# PoE_Si3404.net
KiCad netlist of a schematic drawn in Altium Designer
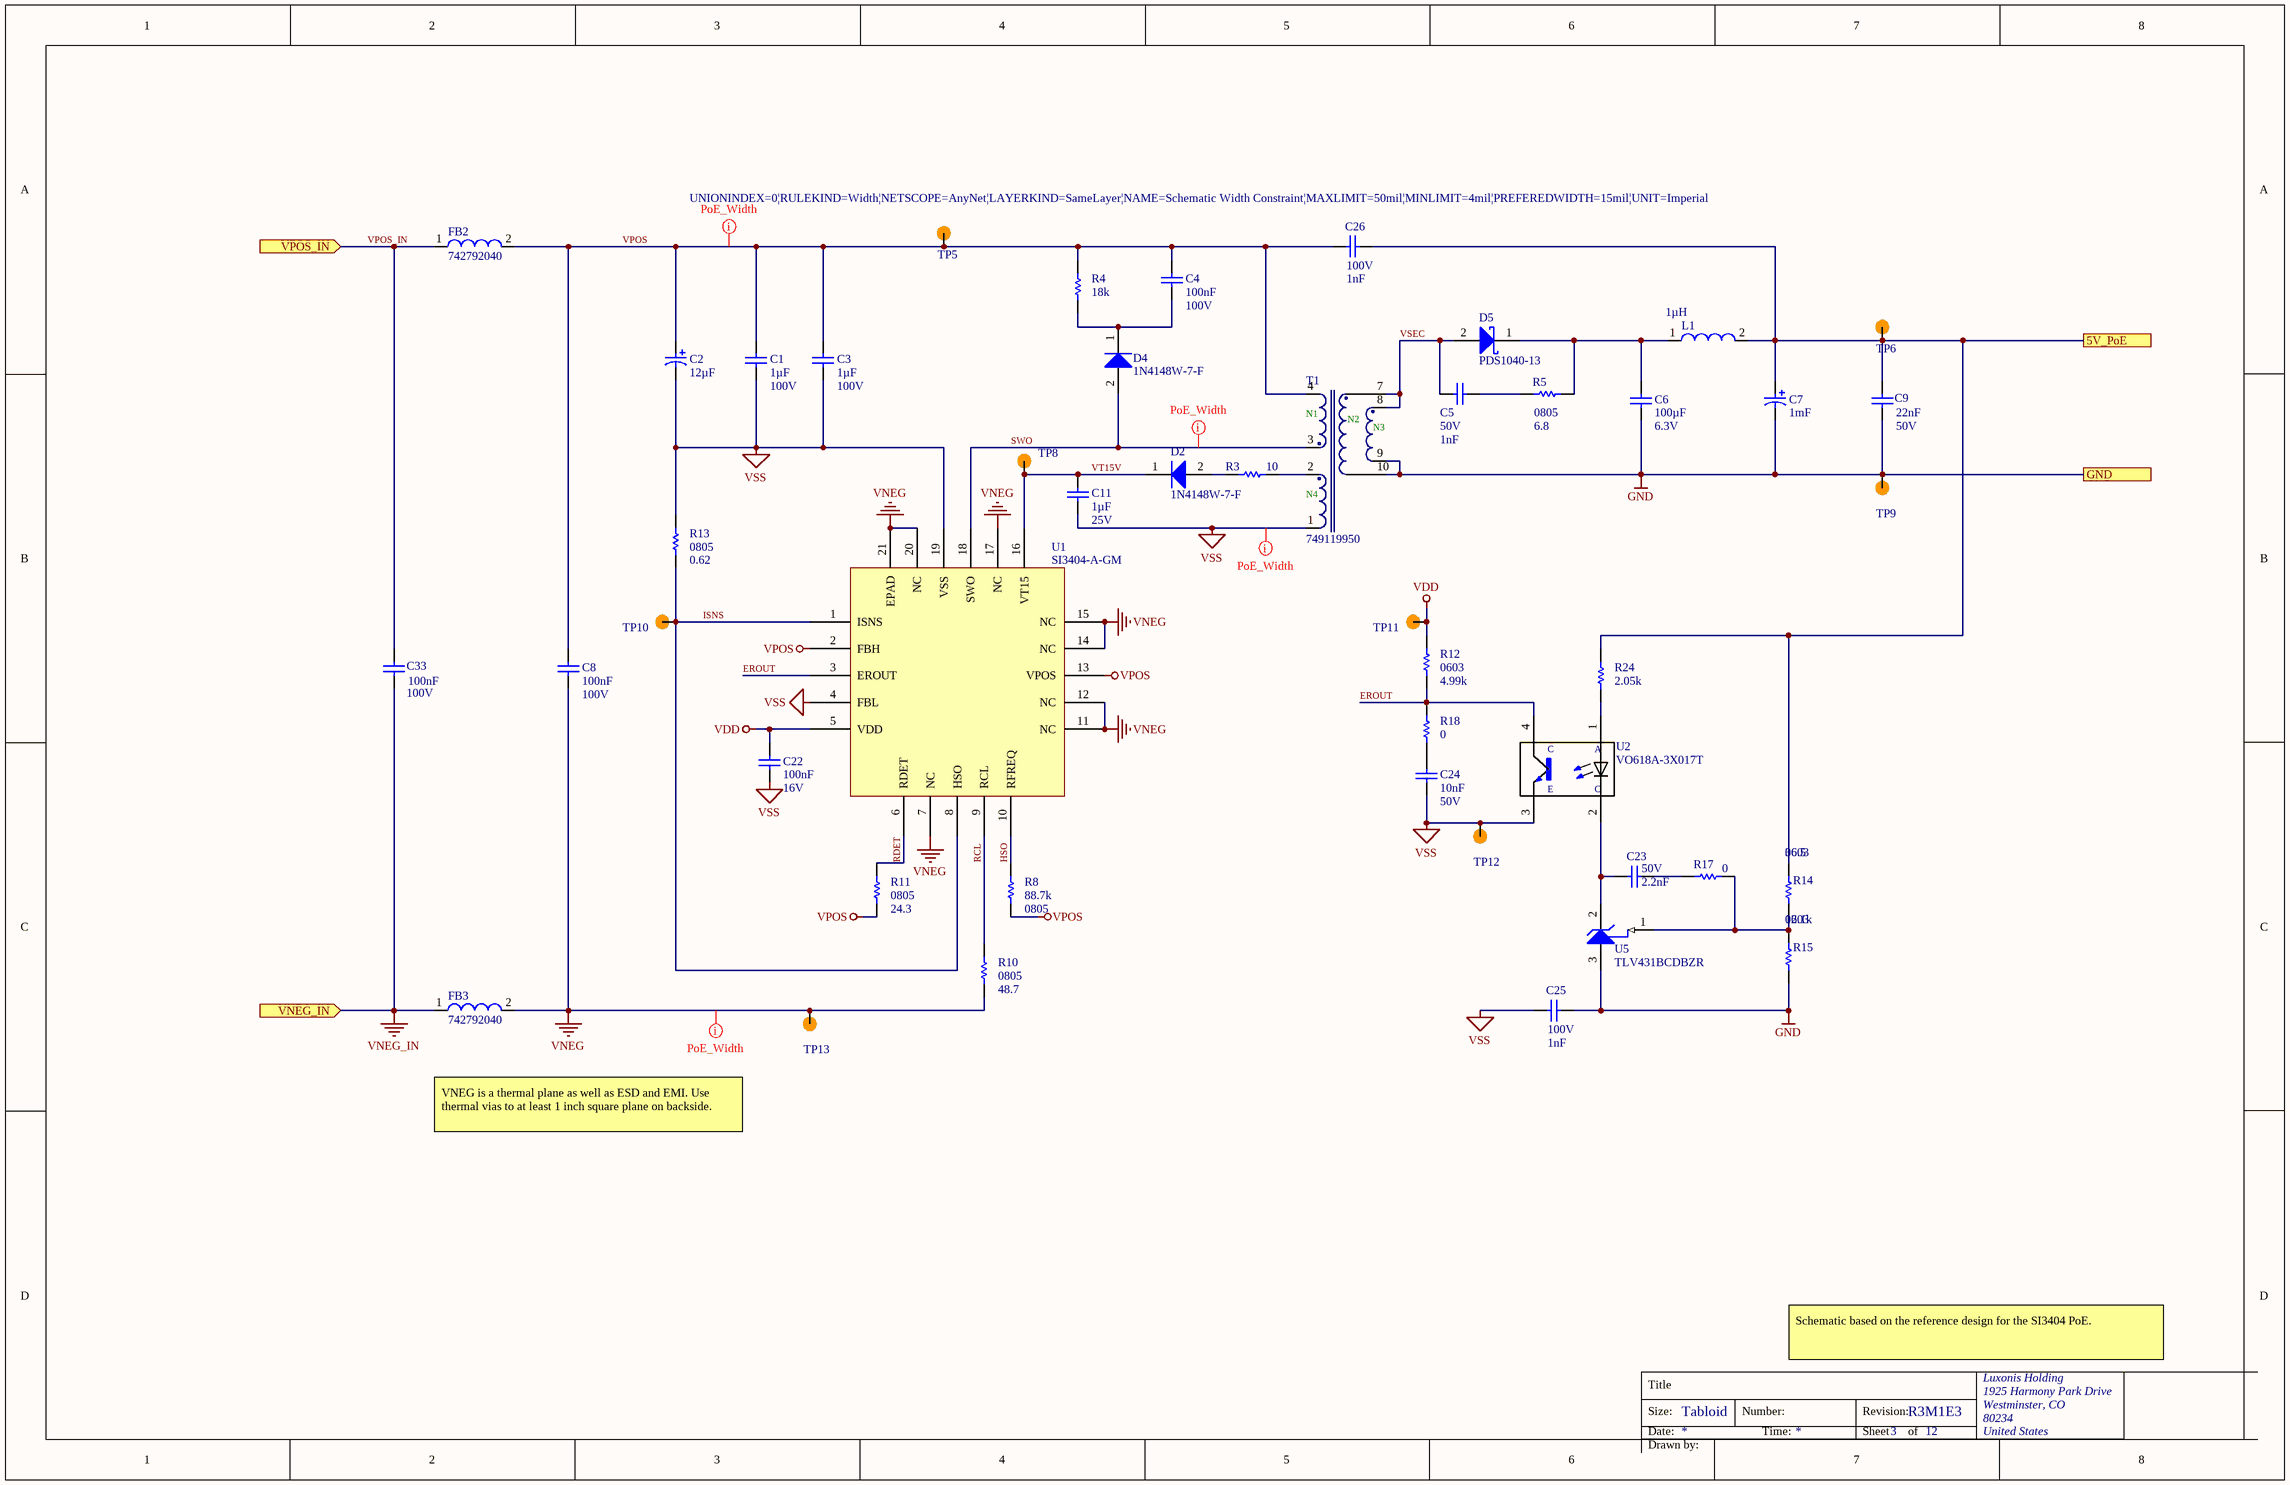
[diagram p0: PoE_Si3404.SchDoc]

(export (version "E")
  (design (tool "Eeschema 10.0.6"))
  (components
    (comp (ref "C1")
      (value "1µF")
      (footprint "CAPC1210(3225)280_N")
      (description "CAP CER 1UF 100V X7R 1210 10%")
      (fields
        (field (name "TOLERANCE") "10%")
        (field (name "VOLTAGE RATING") "100V")
        (field (name "Comment") "CL32B105KCJNNNE")
      )
      (libsource (lib "Luxonis LLC") (part "GRM188R61C475KAAJD"))
    )
    (comp (ref "C2")
      (value "12µF")
      (footprint "EEU-FC2A120")
      (description "CAP ALUM 12UF 100V RADIAL 20%")
      (fields (field (name "TOLERANCE") "20%") (field (name "Comment") "EEU-FC2A120"))
      (libsource (lib "Luxonis LLC") (part "EEU-FC2A120"))
    )
    (comp (ref "C3")
      (value "1µF")
      (footprint "CAPC1210(3225)280_N")
      (description "CAP CER 1UF 100V X7R 1210 10%")
      (fields
        (field (name "TOLERANCE") "10%")
        (field (name "VOLTAGE RATING") "100V")
        (field (name "Comment") "CL32B105KCJNNNE")
      )
      (libsource (lib "Luxonis LLC") (part "GRM188R61C475KAAJD"))
    )
    (comp (ref "C4")
      (value "100nF")
      (footprint "CAPC0805(2012)145_N")
      (description "CAP CER 0.1UF 100V X7R 0805 10%")
      (fields
        (field (name "TOLERANCE") "10%")
        (field (name "VOLTAGE RATING") "100V")
        (field (name "Comment") "CL21B104KCFNNNE")
      )
      (libsource (lib "Luxonis LLC") (part "GRM188R61C475KAAJD"))
    )
    (comp (ref "C5")
      (value "1nF")
      (footprint "CAPC0603(1608)100_N")
      (description "CAP CER 1000PF 50V C0G 0603 1%")
      (fields
        (field (name "TOLERANCE") "1%")
        (field (name "VOLTAGE RATING") "50V")
        (field (name "Comment") "GRM1885C1H102FA01D")
      )
      (libsource (lib "Luxonis LLC") (part "LLL153C70G474ME17E"))
    )
    (comp (ref "C6")
      (value "100µF")
      (footprint "CAPC1206(3216)190_N")
      (description "CAP CER 100UF 6.3V X5R 1206 20%")
      (fields
        (field (name "TOLERANCE") "20%")
        (field (name "VOLTAGE RATING") "6.3V")
        (field (name "Comment") "CL31A107MQHNNNE")
      )
      (libsource (lib "Luxonis LLC") (part "GRM188R61C475KAAJD"))
    )
    (comp (ref "C7")
      (value "1mF")
      (footprint "ECA-0JM102")
      (description "CAP ALUM 1000UF 6.3V RADIAL 20%")
      (fields (field (name "TOLERANCE") "20%") (field (name "Comment") "ECA-0JM102"))
      (libsource (lib "Luxonis LLC") (part "EEU-FC2A120"))
    )
    (comp (ref "C8")
      (value "100nF")
      (footprint "CAPC0805(2012)145_N")
      (description "CAP CER 0.1UF 100V X7R 0805 10%")
      (fields
        (field (name "TOLERANCE") "10%")
        (field (name "VOLTAGE RATING") "100V")
        (field (name "Comment") "CL21B104KCFNNNE")
      )
      (libsource (lib "Luxonis LLC") (part "GRM188R61C475KAAJD"))
    )
    (comp (ref "C9")
      (value "22nF")
      (footprint "CAPC0603(1608)100_N")
      (description "CAP CER 0.022UF 50V X7R 0603 10%")
      (fields
        (field (name "TOLERANCE") "10%")
        (field (name "VOLTAGE RATING") "50V")
        (field (name "Comment") "C0603C223K5RACTU")
      )
      (libsource (lib "Luxonis LLC") (part "LLL153C70G474ME17E"))
    )
    (comp (ref "C11")
      (value "1µF")
      (footprint "CAPC0402(1005)70_N")
      (description "CAP CER 1UF 25V X5R 0402 10%")
      (fields
        (field (name "TOLERANCE") "10%")
        (field (name "VOLTAGE RATING") "25V")
        (field (name "Comment") "GRM155R61E105KA12D")
      )
      (libsource (lib "Luxonis LLC") (part "GRM188R61C475KAAJD"))
    )
    (comp (ref "C22")
      (value "100nF")
      (footprint "CAPC0402(1005)60_N")
      (description "CAP CER 0.1UF 16V X7R 0402 10%")
      (fields
        (field (name "TOLERANCE") "10%")
        (field (name "VOLTAGE RATING") "16V")
        (field (name "Comment") "CL05B104KO5NFNC")
      )
      (libsource (lib "Luxonis LLC") (part "GRM188R61C475KAAJD"))
    )
    (comp (ref "C23")
      (value "2.2nF")
      (footprint "CAPC0603(1608)100_N")
      (description "CAP CER 2200PF 50V C0G 0603 5%")
      (fields
        (field (name "TOLERANCE") "5%")
        (field (name "VOLTAGE RATING") "50V")
        (field (name "Comment") "GRM1885C1H222JA01D")
      )
      (libsource (lib "Luxonis LLC") (part "GRM188R61C475KAAJD"))
    )
    (comp (ref "C24")
      (value "10nF")
      (footprint "CAPC0402(1005)60_N")
      (description "CAP CER 10000PF 50V X7R 0402 10%")
      (fields
        (field (name "TOLERANCE") "10%")
        (field (name "VOLTAGE RATING") "50V")
        (field (name "Comment") "GRM155R71H103KA88D")
      )
      (libsource (lib "Luxonis LLC") (part "GRM188R61C475KAAJD"))
    )
    (comp (ref "C25")
      (value "1nF")
      (footprint "CAPC1206(3216)130_L")
      (description "CAP CER 1nF 2000V X7R 1206 10%")
      (fields
        (field (name "TOLERANCE") "10%")
        (field (name "VOLTAGE RATING") "100V")
        (field (name "Comment") "C1206C102KGRACTU")
      )
      (libsource (lib "Luxonis LLC") (part "LLL153C70G474ME17E"))
    )
    (comp (ref "C26")
      (value "1nF")
      (footprint "CAPC1206(3216)130_L")
      (description "CAP CER 1nF 2000V X7R 1206 10%")
      (fields
        (field (name "TOLERANCE") "10%")
        (field (name "VOLTAGE RATING") "100V")
        (field (name "Comment") "C1206C102KGRACTU")
      )
      (libsource (lib "Luxonis LLC") (part "LLL153C70G474ME17E"))
    )
    (comp (ref "C33")
      (value "100nF")
      (footprint "CAPC0805(2012)145_N")
      (description "CAP CER 0.1UF 100V X7R 0805 10%")
      (fields
        (field (name "TOLERANCE") "10%")
        (field (name "VOLTAGE RATING") "100V")
        (field (name "Comment") "CL21B104KCFNNNE")
      )
      (libsource (lib "Luxonis LLC") (part "GRM188R61C475KAAJD"))
    )
    (comp (ref "D2")
      (value "1N4148W-7-F")
      (footprint "1N4148W-7-F")
      (description "DIODE GEN PURP 100V 300MA SOD123")
      (libsource (lib "Luxonis LLC") (part "1N4148W-7-F"))
    )
    (comp (ref "D4")
      (value "1N4148W-7-F")
      (footprint "RS1B")
      (description "DIODE GEN PURP 100V 1A SMA")
      (libsource (lib "Luxonis LLC") (part "1N4148W-7-F"))
    )
    (comp (ref "D5")
      (value "PDS1040-13")
      (footprint "PDS1040-13")
      (description "DIODE SCHOTTKY 40V 10A POWERDI5")
      (libsource (lib "Luxonis LLC") (part "PDS1040-13"))
    )
    (comp (ref "FB2")
      (value "742792040")
      (footprint "742792040")
      (description "FERRITE BEAD 600 OHM 0805 1LN")
      (fields (field (name "TOLERANCE") "25%"))
      (libsource (lib "Luxonis LLC") (part "742792040"))
    )
    (comp (ref "FB3")
      (value "742792040")
      (footprint "742792040")
      (description "FERRITE BEAD 600 OHM 0805 1LN")
      (fields (field (name "TOLERANCE") "25%"))
      (libsource (lib "Luxonis LLC") (part "742792040"))
    )
    (comp (ref "L1")
      (value "1µH")
      (footprint "DO1608C-102MLx")
      (description "IND POWER WIREWOUND 1uH 20% 100KHz FERRITE 2.7A")
      (fields (field (name "TOLERANCE") "20%") (field (name "Comment") "DO1608C-102ML"))
      (libsource (lib "Luxonis LLC") (part "DFE252012P-1R0M=P2"))
    )
    (comp (ref "R3")
      (value "10")
      (footprint "RESC0603(1608)_N")
      (description "RES SMD 10 OHM 1% 1/10W 0603")
      (fields (field (name "TOLERANCE") "1%") (field (name "Comment") "CRCW060310R0FKEA"))
      (libsource (lib "Luxonis LLC") (part "RC0402FR-0722RL_1"))
    )
    (comp (ref "R4")
      (value "18k")
      (footprint "RESC0603(1608)_N")
      (description "RES SMD 18K OHM 5% 1/10W 0603")
      (fields (field (name "TOLERANCE") "5%") (field (name "Comment") "RC0603JR-0718KL"))
      (libsource (lib "Luxonis LLC") (part "RC0402FR-0722RL_1"))
    )
    (comp (ref "R5")
      (value "6.8")
      (footprint "RESC0805(2012)_N")
      (description "RES SMD 6.8 OHM 1% 1/8W 0805")
      (fields
        (field (name "CASE/PACKAGE") "0805")
        (field (name "TOLERANCE") "1%")
        (field (name "Comment") "RC0805FR-076R8L")
      )
      (libsource (lib "Luxonis LLC") (part "Default resistor symbol"))
    )
    (comp (ref "R8")
      (value "88.7k")
      (footprint "RESC0805(2012)_N")
      (description "RES SMD 88.7K OHM 1% 1/8W 0805")
      (fields
        (field (name "CASE/PACKAGE") "0805")
        (field (name "TOLERANCE") "1%")
        (field (name "Comment") "CRCW080588K7FKEA")
      )
      (libsource (lib "Luxonis LLC") (part "Default resistor symbol"))
    )
    (comp (ref "R10")
      (value "48.7")
      (footprint "RESC0805(2012)_N")
      (description "RES SMD 48.7 OHM 1% 1/8W 0805")
      (fields
        (field (name "CASE/PACKAGE") "0805")
        (field (name "TOLERANCE") "1%")
        (field (name "Comment") "RC0805FR-0748R7L")
      )
      (libsource (lib "Luxonis LLC") (part "Default resistor symbol"))
    )
    (comp (ref "R11")
      (value "24.3")
      (footprint "RESC0805(2012)_N")
      (description "RES SMD 24.3K OHM 1% 1/8W 0805")
      (fields
        (field (name "CASE/PACKAGE") "0805")
        (field (name "TOLERANCE") "1%")
        (field (name "Comment") "CRCW080524K3FKEA")
      )
      (libsource (lib "Luxonis LLC") (part "Default resistor symbol"))
    )
    (comp (ref "R12")
      (value "4.99k")
      (footprint "RESC0603(1608)_N")
      (description "RES SMD 4.99K OHM 1% 1/10W 0603")
      (fields
        (field (name "CASE/PACKAGE") "0603")
        (field (name "TOLERANCE") "1%")
        (field (name "Comment") "RC0603FR-074K99L")
      )
      (libsource (lib "Luxonis LLC") (part "Default resistor symbol"))
    )
    (comp (ref "R13")
      (value "0.62")
      (footprint "RESC0805(2012)_N")
      (description "RES SMD 620 MOHM 1% 1/8W 0805")
      (fields
        (field (name "CASE/PACKAGE") "0805")
        (field (name "TOLERANCE") "1%")
        (field (name "Comment") "RL0805FR-070R62L")
      )
      (libsource (lib "Luxonis LLC") (part "Default resistor symbol"))
    )
    (comp (ref "R14")
      (value "36.5")
      (footprint "RESC0603(1608)_N")
      (description "RES SMD 36.5K OHM 1% 1/10W 0603")
      (fields
        (field (name "CASE/PACKAGE") "0603")
        (field (name "TOLERANCE") "1%")
        (field (name "Comment") "RC0603FR-0736K5L")
      )
      (libsource (lib "Luxonis LLC") (part "Default resistor symbol"))
    )
    (comp (ref "R15")
      (value "12.1k")
      (footprint "RESC0603(1608)_N")
      (description "RES SMD 12.1K OHM 1% 1/10W 0603")
      (fields
        (field (name "CASE/PACKAGE") "0603")
        (field (name "TOLERANCE") "1%")
        (field (name "Comment") "RC0603FR-0712K1L")
      )
      (libsource (lib "Luxonis LLC") (part "Default resistor symbol"))
    )
    (comp (ref "R17")
      (value "0")
      (footprint "RESC0603(1608)_N")
      (description "RES SMD 0 OHM 5% 1/10W 0603")
      (fields (field (name "TOLERANCE") "5%") (field (name "Comment") "CRCW06030000Z0EA"))
      (libsource (lib "Luxonis LLC") (part "RC0402FR-0722RL_1"))
    )
    (comp (ref "R18")
      (value "0")
      (footprint "RESC0603(1608)_N")
      (description "RES SMD 0 OHM 5% 1/10W 0603")
      (fields (field (name "TOLERANCE") "5%") (field (name "Comment") "CRCW06030000Z0EA"))
      (libsource (lib "Luxonis LLC") (part "RC0402FR-0722RL_1"))
    )
    (comp (ref "R24")
      (value "2.05k")
      (footprint "RESC0603(1608)_N")
      (description "RES SMD 2.05K OHM 1% 1/10W 0603")
      (fields (field (name "TOLERANCE") "1%") (field (name "Comment") "RC0603FR-072K05L"))
      (libsource (lib "Luxonis LLC") (part "RC0402FR-0722RL_1"))
    )
    (comp (ref "T1")
      (value "749119950")
      (footprint "749119950")
      (description "TRANS FLYBACK POE 127UH SMD")
      (libsource (lib "Luxonis LLC") (part "749119950"))
    )
    (comp (ref "TP5")
      (value "TEST_POINT")
      (footprint "TP100_200_NS")
      (libsource (lib "Luxonis LLC") (part "TEST_POINT"))
    )
    (comp (ref "TP6")
      (value "TEST_POINT")
      (footprint "TP100_200_NS")
      (libsource (lib "Luxonis LLC") (part "TEST_POINT"))
    )
    (comp (ref "TP8")
      (value "TEST_POINT")
      (footprint "TP100_200_NS")
      (libsource (lib "Luxonis LLC") (part "TEST_POINT"))
    )
    (comp (ref "TP9")
      (value "TEST_POINT")
      (footprint "TP100_200_NS")
      (libsource (lib "Luxonis LLC") (part "TEST_POINT"))
    )
    (comp (ref "TP10")
      (value "TEST_POINT")
      (footprint "TP100_200_NS")
      (libsource (lib "Luxonis LLC") (part "TEST_POINT"))
    )
    (comp (ref "TP11")
      (value "TEST_POINT")
      (footprint "TP100_200_NS")
      (libsource (lib "Luxonis LLC") (part "TEST_POINT"))
    )
    (comp (ref "TP12")
      (value "TEST_POINT")
      (footprint "TP100_200_NS")
      (libsource (lib "Luxonis LLC") (part "TEST_POINT"))
    )
    (comp (ref "TP13")
      (value "TEST_POINT")
      (footprint "TP100_200_NS")
      (libsource (lib "Luxonis LLC") (part "TEST_POINT"))
    )
    (comp (ref "U1")
      (value "SI3404-A-GM")
      (footprint "Si3404-A-GM")
      (description "IC POE CNTRL 1 CHANNEL 20QFN")
      (libsource (lib "Luxonis LLC") (part "SI3404-A-GM"))
    )
    (comp (ref "U2")
      (value "VO618A-3X017T")
      (footprint "VO618A-3X017T")
      (description "OPTOISOLATOR 5.3KV TRANS 4-SMD")
      (libsource (lib "Luxonis LLC") (part "VO618A-3X017T"))
    )
    (comp (ref "U5")
      (value "TLV431BCDBZR")
      (footprint "TLV431BCDBZR")
      (description "IC VREF SHUNT ADJ SOT23-3")
      (libsource (lib "Luxonis LLC") (part "TLV431BCDBZR"))
    )
  )
  (nets
    (net (code "1") (name "/5V_PoE") (class "Default")
      (node (ref "C26") (pin "2") (pinfunction "2_2") (pintype "passive"))
      (node (ref "C7") (pin "1") (pinfunction "1_1") (pintype "passive"))
      (node (ref "C9") (pin "2") (pinfunction "2_2") (pintype "passive"))
      (node (ref "L1") (pin "2") (pinfunction "2_2") (pintype "passive"))
      (node (ref "R14") (pin "2") (pinfunction "2_2") (pintype "passive"))
      (node (ref "R24") (pin "2") (pinfunction "2_2") (pintype "passive"))
      (node (ref "TP6") (pin "1") (pintype "passive"))
    )
    (net (code "2") (name "/EROUT") (class "Default")
      (node (ref "R12") (pin "1") (pinfunction "1_1") (pintype "passive"))
      (node (ref "R18") (pin "2") (pinfunction "2_2") (pintype "passive"))
      (node (ref "U1") (pin "3") (pinfunction "EROUT_3") (pintype "passive"))
      (node (ref "U2") (pin "4") (pinfunction "CO_4") (pintype "passive"))
    )
    (net (code "3") (name "/HSO") (class "Default")
      (node (ref "R8") (pin "2") (pinfunction "2_2") (pintype "passive"))
      (node (ref "U1") (pin "10") (pinfunction "RFREQ_10") (pintype "passive"))
    )
    (net (code "4") (name "/ISNS") (class "Default")
      (node (ref "R13") (pin "1") (pinfunction "1_1") (pintype "passive"))
      (node (ref "TP10") (pin "1") (pintype "passive"))
      (node (ref "U1") (pin "1") (pinfunction "ISNS_1") (pintype "passive"))
      (node (ref "U1") (pin "8") (pinfunction "HSO_8") (pintype "passive"))
    )
    (net (code "5") (name "/RCL") (class "Default")
      (node (ref "R10") (pin "2") (pinfunction "2_2") (pintype "passive"))
      (node (ref "U1") (pin "9") (pinfunction "RCL_9") (pintype "passive"))
    )
    (net (code "6") (name "/RDET") (class "Default")
      (node (ref "R11") (pin "2") (pinfunction "2_2") (pintype "passive"))
      (node (ref "U1") (pin "6") (pinfunction "RDET_6") (pintype "passive"))
    )
    (net (code "7") (name "/SWO") (class "Default")
      (node (ref "D4") (pin "2") (pinfunction "A_2") (pintype "passive"))
      (node (ref "T1") (pin "3") (pinfunction "3_3") (pintype "passive"))
      (node (ref "U1") (pin "18") (pinfunction "SWO_18") (pintype "passive"))
    )
    (net (code "8") (name "/VPOS_IN") (class "Default")
      (node (ref "C33") (pin "2") (pinfunction "2_2") (pintype "passive"))
      (node (ref "FB2") (pin "1") (pinfunction "1_1") (pintype "passive"))
    )
    (net (code "9") (name "/VSEC") (class "Default")
      (node (ref "C5") (pin "2") (pinfunction "2_2") (pintype "passive"))
      (node (ref "D5") (pin "2") (pinfunction "A_2") (pintype "passive"))
      (node (ref "T1") (pin "7") (pinfunction "7_7") (pintype "passive"))
      (node (ref "T1") (pin "8") (pinfunction "8_8") (pintype "passive"))
    )
    (net (code "10") (name "/VT15V") (class "Default")
      (node (ref "C11") (pin "2") (pinfunction "2_2") (pintype "passive"))
      (node (ref "D2") (pin "1") (pinfunction "K_1") (pintype "passive"))
      (node (ref "TP8") (pin "1") (pintype "passive"))
      (node (ref "U1") (pin "16") (pinfunction "VT15_16") (pintype "passive"))
    )
    (net (code "11") (name "GND") (class "Default")
      (node (ref "C25") (pin "2") (pinfunction "2_2") (pintype "passive"))
      (node (ref "C6") (pin "1") (pinfunction "1_1") (pintype "passive"))
      (node (ref "C7") (pin "2") (pinfunction "2_2") (pintype "passive"))
      (node (ref "C9") (pin "1") (pinfunction "1_1") (pintype "passive"))
      (node (ref "R15") (pin "1") (pinfunction "1_1") (pintype "passive"))
      (node (ref "T1") (pin "10") (pinfunction "10_10") (pintype "passive"))
      (node (ref "T1") (pin "9") (pinfunction "9_9") (pintype "passive"))
      (node (ref "TP9") (pin "1") (pintype "passive"))
      (node (ref "U5") (pin "3") (pinfunction "ANODE_3") (pintype "passive"))
    )
    (net (code "12") (name "Net-(C5-Pad1)") (class "Default")
      (node (ref "C5") (pin "1") (pinfunction "1_1") (pintype "passive"))
      (node (ref "R5") (pin "1") (pinfunction "1_1") (pintype "passive"))
    )
    (net (code "13") (name "Net-(C23-Pad2)") (class "Default")
      (node (ref "C23") (pin "2") (pinfunction "2_2") (pintype "passive"))
      (node (ref "R17") (pin "2") (pinfunction "2_2") (pintype "passive"))
    )
    (net (code "14") (name "Net-(C24-Pad2)") (class "Default")
      (node (ref "C24") (pin "2") (pinfunction "2_2") (pintype "passive"))
      (node (ref "R18") (pin "1") (pinfunction "1_1") (pintype "passive"))
    )
    (net (code "15") (name "Net-(D2-A)") (class "Default")
      (node (ref "D2") (pin "2") (pinfunction "A_2") (pintype "passive"))
      (node (ref "R3") (pin "1") (pinfunction "1_1") (pintype "passive"))
    )
    (net (code "16") (name "Net-(D4-K)") (class "Default")
      (node (ref "C4") (pin "1") (pinfunction "1_1") (pintype "passive"))
      (node (ref "D4") (pin "1") (pinfunction "K_1") (pintype "passive"))
      (node (ref "R4") (pin "1") (pinfunction "1_1") (pintype "passive"))
    )
    (net (code "17") (name "Net-(D5-K)") (class "Default")
      (node (ref "C6") (pin "2") (pinfunction "2_2") (pintype "passive"))
      (node (ref "D5") (pin "1") (pinfunction "K_1") (pintype "passive"))
      (node (ref "L1") (pin "1") (pinfunction "1_1") (pintype "passive"))
      (node (ref "R5") (pin "2") (pinfunction "2_2") (pintype "passive"))
    )
    (net (code "18") (name "Net-(R3-Pad2)") (class "Default")
      (node (ref "R3") (pin "2") (pinfunction "2_2") (pintype "passive"))
      (node (ref "T1") (pin "2") (pinfunction "2_2") (pintype "passive"))
    )
    (net (code "19") (name "Net-(U2-A)") (class "Default")
      (node (ref "R24") (pin "1") (pinfunction "1_1") (pintype "passive"))
      (node (ref "U2") (pin "1") (pinfunction "A_1") (pintype "passive"))
    )
    (net (code "20") (name "Net-(U2-C)") (class "Default")
      (node (ref "C23") (pin "1") (pinfunction "1_1") (pintype "passive"))
      (node (ref "U2") (pin "2") (pinfunction "C_2") (pintype "passive"))
      (node (ref "U5") (pin "2") (pinfunction "CATHODE_2") (pintype "passive"))
    )
    (net (code "21") (name "Net-(U5-REF)") (class "Default")
      (node (ref "R14") (pin "1") (pinfunction "1_1") (pintype "passive"))
      (node (ref "R15") (pin "2") (pinfunction "2_2") (pintype "passive"))
      (node (ref "R17") (pin "1") (pinfunction "1_1") (pintype "passive"))
      (node (ref "U5") (pin "1") (pinfunction "REF_1") (pintype "input"))
    )
    (net (code "22") (name "VDD") (class "Default")
      (node (ref "C22") (pin "2") (pinfunction "2_2") (pintype "passive"))
      (node (ref "R12") (pin "2") (pinfunction "2_2") (pintype "passive"))
      (node (ref "TP11") (pin "1") (pintype "passive"))
      (node (ref "U1") (pin "5") (pinfunction "VDD_5") (pintype "passive"))
    )
    (net (code "23") (name "VNEG") (class "Default")
      (node (ref "C8") (pin "1") (pinfunction "1_1") (pintype "passive"))
      (node (ref "FB3") (pin "2") (pinfunction "2_2") (pintype "passive"))
      (node (ref "R10") (pin "1") (pinfunction "1_1") (pintype "passive"))
      (node (ref "TP13") (pin "1") (pintype "passive"))
      (node (ref "U1") (pin "11") (pinfunction "NC_11") (pintype "passive"))
      (node (ref "U1") (pin "12") (pinfunction "NC_12") (pintype "passive"))
      (node (ref "U1") (pin "14") (pinfunction "NC_14") (pintype "passive"))
      (node (ref "U1") (pin "15") (pinfunction "NC_15") (pintype "passive"))
      (node (ref "U1") (pin "17") (pinfunction "NC_17") (pintype "passive"))
      (node (ref "U1") (pin "20") (pinfunction "NC_20") (pintype "passive"))
      (node (ref "U1") (pin "21") (pinfunction "EPAD_21") (pintype "passive"))
      (node (ref "U1") (pin "7") (pinfunction "NC_7") (pintype "passive"))
    )
    (net (code "24") (name "VNEG_IN") (class "Default")
      (node (ref "C33") (pin "1") (pinfunction "1_1") (pintype "passive"))
      (node (ref "FB3") (pin "1") (pinfunction "1_1") (pintype "passive"))
    )
    (net (code "25") (name "VPOS") (class "Default")
      (node (ref "C1") (pin "2") (pinfunction "2_2") (pintype "passive"))
      (node (ref "C2") (pin "1") (pinfunction "1_1") (pintype "passive"))
      (node (ref "C26") (pin "1") (pinfunction "1_1") (pintype "passive"))
      (node (ref "C3") (pin "2") (pinfunction "2_2") (pintype "passive"))
      (node (ref "C4") (pin "2") (pinfunction "2_2") (pintype "passive"))
      (node (ref "C8") (pin "2") (pinfunction "2_2") (pintype "passive"))
      (node (ref "FB2") (pin "2") (pinfunction "2_2") (pintype "passive"))
      (node (ref "R11") (pin "1") (pinfunction "1_1") (pintype "passive"))
      (node (ref "R4") (pin "2") (pinfunction "2_2") (pintype "passive"))
      (node (ref "R8") (pin "1") (pinfunction "1_1") (pintype "passive"))
      (node (ref "T1") (pin "4") (pinfunction "4_4") (pintype "passive"))
      (node (ref "TP5") (pin "1") (pintype "passive"))
      (node (ref "U1") (pin "13") (pinfunction "VPOS_13") (pintype "passive"))
      (node (ref "U1") (pin "2") (pinfunction "FBH_2") (pintype "passive"))
    )
    (net (code "26") (name "VSS") (class "Default")
      (node (ref "C1") (pin "1") (pinfunction "1_1") (pintype "passive"))
      (node (ref "C11") (pin "1") (pinfunction "1_1") (pintype "passive"))
      (node (ref "C2") (pin "2") (pinfunction "2_2") (pintype "passive"))
      (node (ref "C22") (pin "1") (pinfunction "1_1") (pintype "passive"))
      (node (ref "C24") (pin "1") (pinfunction "1_1") (pintype "passive"))
      (node (ref "C25") (pin "1") (pinfunction "1_1") (pintype "passive"))
      (node (ref "C3") (pin "1") (pinfunction "1_1") (pintype "passive"))
      (node (ref "R13") (pin "2") (pinfunction "2_2") (pintype "passive"))
      (node (ref "T1") (pin "1") (pinfunction "1_1") (pintype "passive"))
      (node (ref "TP12") (pin "1") (pintype "passive"))
      (node (ref "U1") (pin "19") (pinfunction "VSS_19") (pintype "passive"))
      (node (ref "U1") (pin "4") (pinfunction "FBL_4") (pintype "passive"))
      (node (ref "U2") (pin "3") (pinfunction "E_3") (pintype "passive"))
    )
  )
)
